# finger_circuit.net
KiCad netlist of a schematic drawn in EAGLE
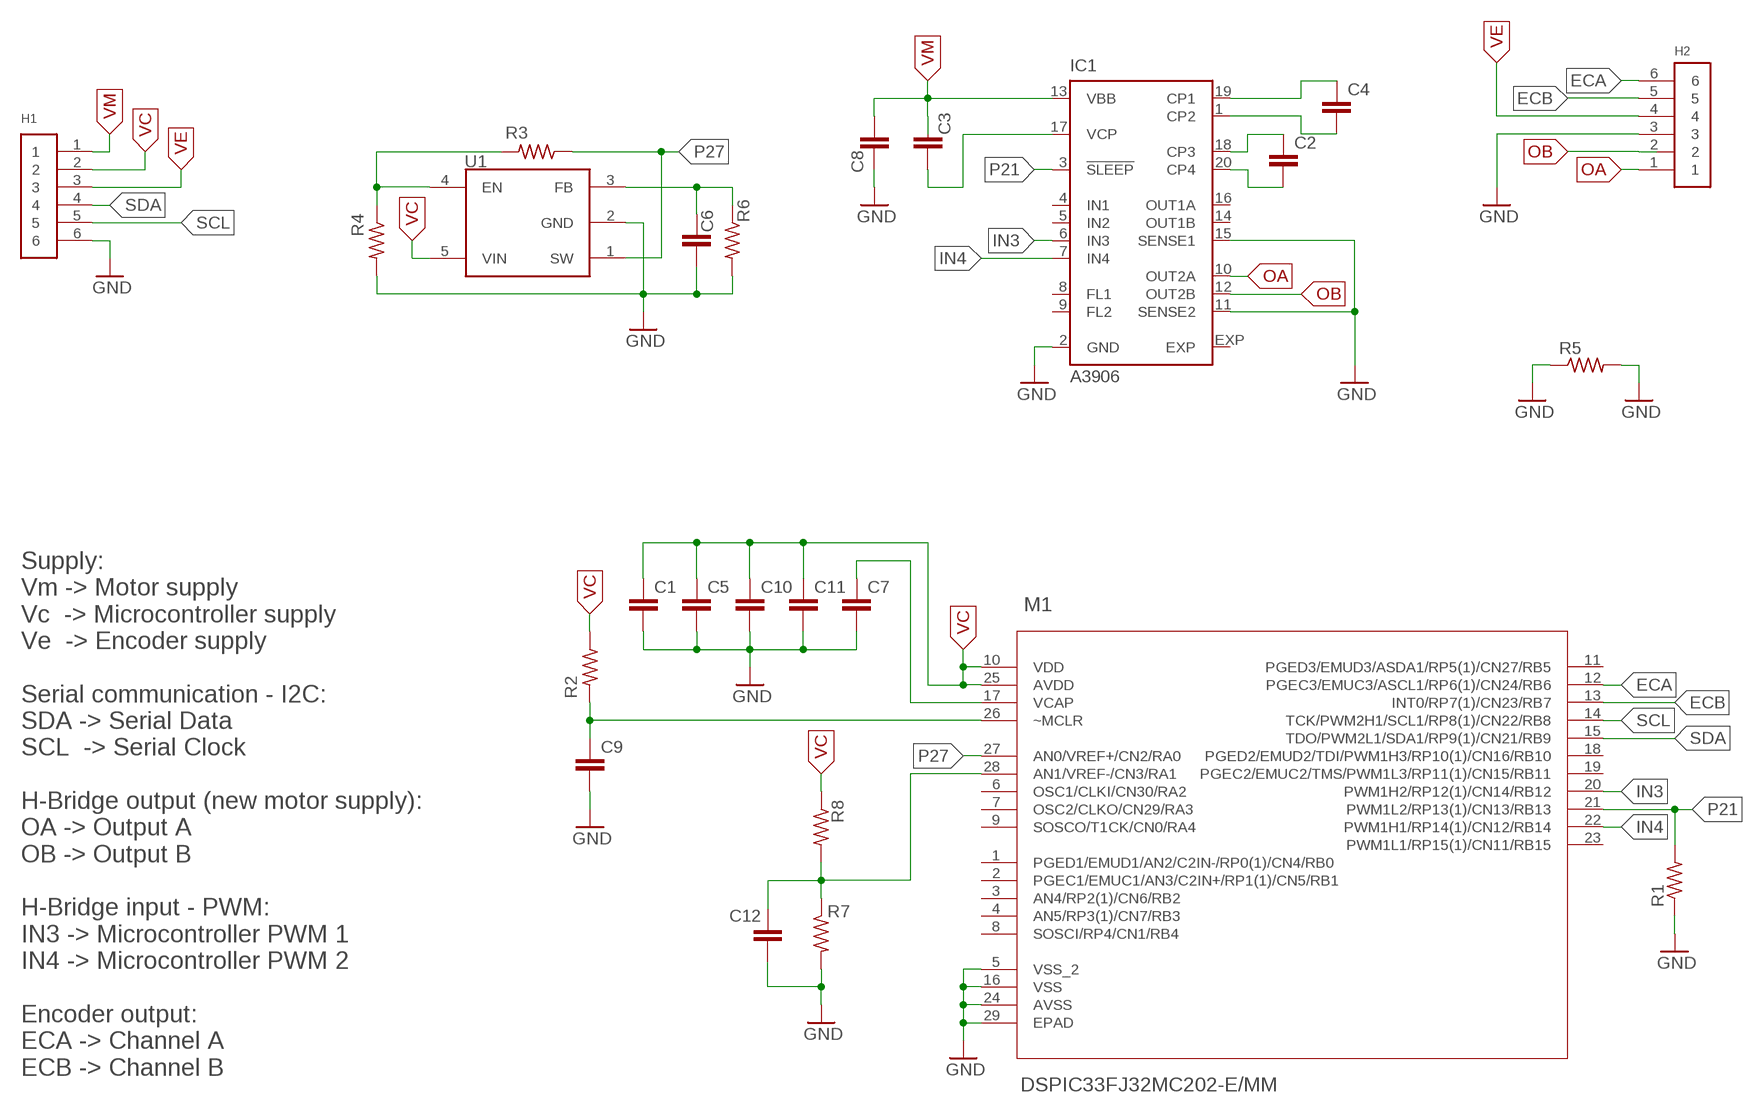
[diagram p0: schematic, sheet 1]

(export (version "E")
  (design (tool "Eeschema 10.0.6"))
  (components
    (comp (ref "C1")
      (value "CAPACITOR_0805_M")
      (footprint "eagle-import:RESC0805_M")
      (libsource (lib "eagle-import") (part "CAPACITOR_0805_M"))
    )
    (comp (ref "C2")
      (value "CAPACITOR_0805_M")
      (footprint "eagle-import:RESC0805_M")
      (libsource (lib "eagle-import") (part "CAPACITOR_0805_M"))
    )
    (comp (ref "C3")
      (value "CAPACITOR_0805_M")
      (footprint "eagle-import:RESC0805_M")
      (libsource (lib "eagle-import") (part "CAPACITOR_0805_M"))
    )
    (comp (ref "C4")
      (value "CAPACITOR_0805_M")
      (footprint "eagle-import:RESC0805_M")
      (libsource (lib "eagle-import") (part "CAPACITOR_0805_M"))
    )
    (comp (ref "C5")
      (value "CAPACITOR_0805_M")
      (footprint "eagle-import:RESC0805_M")
      (libsource (lib "eagle-import") (part "CAPACITOR_0805_M"))
    )
    (comp (ref "C6")
      (value "CAPACITOR_0805_M")
      (footprint "eagle-import:RESC0805_M")
      (libsource (lib "eagle-import") (part "CAPACITOR_0805_M"))
    )
    (comp (ref "C7")
      (value "CAPACITOR_0805_M")
      (footprint "eagle-import:RESC0805_M")
      (libsource (lib "eagle-import") (part "CAPACITOR_0805_M"))
    )
    (comp (ref "C8")
      (value "CAPACITOR_0805_M")
      (footprint "eagle-import:RESC0805_M")
      (libsource (lib "eagle-import") (part "CAPACITOR_0805_M"))
    )
    (comp (ref "C9")
      (value "CAPACITOR_0805_M")
      (footprint "eagle-import:RESC0805_M")
      (libsource (lib "eagle-import") (part "CAPACITOR_0805_M"))
    )
    (comp (ref "C10")
      (value "CAPACITOR_0805_M")
      (footprint "eagle-import:RESC0805_M")
      (libsource (lib "eagle-import") (part "CAPACITOR_0805_M"))
    )
    (comp (ref "C11")
      (value "CAPACITOR_0805_M")
      (footprint "eagle-import:RESC0805_M")
      (libsource (lib "eagle-import") (part "CAPACITOR_0805_M"))
    )
    (comp (ref "C12")
      (value "CAPACITOR_0805_M")
      (footprint "eagle-import:RESC0805_M")
      (libsource (lib "eagle-import") (part "CAPACITOR_0805_M"))
    )
    (comp (ref "H1")
      (value "61300611121")
      (footprint "eagle-import:61300611121")
      (fields
        (field (name "DIGI_KEY_PART_NUMBER") "732-5319-ND")
        (field (name "MANUFACTURER") "Wurth Electronics Inc.")
        (field (name "CREATED_BY") "PCBLayout.com")
      )
      (libsource (lib "eagle-import") (part "61300611121"))
    )
    (comp (ref "H2")
      (value "61300611121")
      (footprint "eagle-import:61300611121")
      (fields
        (field (name "DIGI_KEY_PART_NUMBER") "732-5319-ND")
        (field (name "MANUFACTURER") "Wurth Electronics Inc.")
        (field (name "CREATED_BY") "PCBLayout.com")
      )
      (libsource (lib "eagle-import") (part "61300611121"))
    )
    (comp (ref "IC1")
      (value "A3906")
      (footprint "eagle-import:QFN20")
      (libsource (lib "eagle-import") (part "A3906"))
    )
    (comp (ref "M1")
      (value "DSPIC33FJ32MC202-E/MM")
      (footprint "eagle-import:QFN65P600X600X100-29N")
      (fields
        (field (name "DIGI-KEY_PART_NUMBER") "DSPIC33FJ32MC202-E/MM-ND")
        (field (name "MF") "Microchip")
      )
      (libsource (lib "eagle-import") (part "DSPIC33FJ32MC202-E/MM"))
    )
    (comp (ref "R1")
      (value "R-US_R0805")
      (footprint "eagle-import:R0805")
      (libsource (lib "eagle-import") (part "R-US_R0805"))
    )
    (comp (ref "R2")
      (value "R-US_R0805")
      (footprint "eagle-import:R0805")
      (libsource (lib "eagle-import") (part "R-US_R0805"))
    )
    (comp (ref "R3")
      (value "R-US_R0805")
      (footprint "eagle-import:R0805")
      (libsource (lib "eagle-import") (part "R-US_R0805"))
    )
    (comp (ref "R4")
      (value "R-US_R0805")
      (footprint "eagle-import:R0805")
      (libsource (lib "eagle-import") (part "R-US_R0805"))
    )
    (comp (ref "R5")
      (value "R-US_R0805")
      (footprint "eagle-import:R0805")
      (libsource (lib "eagle-import") (part "R-US_R0805"))
    )
    (comp (ref "R6")
      (value "R-US_R0805")
      (footprint "eagle-import:R0805")
      (libsource (lib "eagle-import") (part "R-US_R0805"))
    )
    (comp (ref "R7")
      (value "R-US_R0805")
      (footprint "eagle-import:R0805")
      (libsource (lib "eagle-import") (part "R-US_R0805"))
    )
    (comp (ref "R8")
      (value "R-US_R0805")
      (footprint "eagle-import:R0805")
      (libsource (lib "eagle-import") (part "R-US_R0805"))
    )
    (comp (ref "U1")
      (value "LMR10510")
      (footprint "eagle-import:SOT-23-5")
      (fields
        (field (name "DIGIKEY_PART_NUMBER") "LMR10510YMFE/NOPBTR-ND")
        (field (name "MANUFACTURER") "Texas Instruments")
        (field (name "MPN") "LMR10510YMFE/NOPB")
        (field (name "CREATED_BY") "PCBLayout.com")
      )
      (libsource (lib "eagle-import") (part "LMR10510YMFE/NOPB"))
    )
  )
  (nets
    (net (code "1") (name "ECA") (class "Default")
      (node (ref "H2") (pin "6") (pinfunction "6_6") (pintype "passive"))
      (node (ref "M1") (pin "12") (pinfunction "PGEC3/EMUC3/ASCL1/RP6(1)/CN24/RB6_12") (pintype "bidirectional"))
    )
    (net (code "2") (name "ECB") (class "Default")
      (node (ref "H2") (pin "5") (pinfunction "5_5") (pintype "passive"))
      (node (ref "M1") (pin "13") (pinfunction "INT0/RP7(1)/CN23/RB7_13") (pintype "bidirectional"))
    )
    (net (code "3") (name "GND") (class "Default")
      (node (ref "C1") (pin "2") (pinfunction "2_2") (pintype "passive"))
      (node (ref "C10") (pin "2") (pinfunction "2_2") (pintype "passive"))
      (node (ref "C11") (pin "2") (pinfunction "2_2") (pintype "passive"))
      (node (ref "C12") (pin "2") (pinfunction "2_2") (pintype "passive"))
      (node (ref "C5") (pin "2") (pinfunction "2_2") (pintype "passive"))
      (node (ref "C6") (pin "2") (pinfunction "2_2") (pintype "passive"))
      (node (ref "C7") (pin "2") (pinfunction "2_2") (pintype "passive"))
      (node (ref "C8") (pin "1") (pinfunction "1_1") (pintype "passive"))
      (node (ref "C9") (pin "2") (pinfunction "2_2") (pintype "passive"))
      (node (ref "H1") (pin "6") (pinfunction "6_6") (pintype "passive"))
      (node (ref "H2") (pin "3") (pinfunction "3_3") (pintype "passive"))
      (node (ref "IC1") (pin "11") (pinfunction "SENSE2_11") (pintype "input"))
      (node (ref "IC1") (pin "15") (pinfunction "SENSE1_15") (pintype "input"))
      (node (ref "IC1") (pin "2") (pinfunction "GND_2") (pintype "power_in"))
      (node (ref "M1") (pin "16") (pinfunction "VSS_16") (pintype "power_in"))
      (node (ref "M1") (pin "24") (pinfunction "AVSS_24") (pintype "power_in"))
      (node (ref "M1") (pin "29") (pinfunction "EPAD_29") (pintype "passive"))
      (node (ref "M1") (pin "5") (pinfunction "VSS_2_5") (pintype "power_in"))
      (node (ref "R1") (pin "1") (pinfunction "1_1") (pintype "passive"))
      (node (ref "R4") (pin "2") (pinfunction "2_2") (pintype "passive"))
      (node (ref "R5") (pin "1") (pinfunction "1_1") (pintype "passive"))
      (node (ref "R5") (pin "2") (pinfunction "2_2") (pintype "passive"))
      (node (ref "R6") (pin "2") (pinfunction "2_2") (pintype "passive"))
      (node (ref "R7") (pin "2") (pinfunction "2_2") (pintype "passive"))
      (node (ref "U1") (pin "2") (pinfunction "GND_2") (pintype "power_in"))
    )
    (net (code "4") (name "IN3") (class "Default")
      (node (ref "IC1") (pin "6") (pinfunction "IN3_6") (pintype "input"))
      (node (ref "M1") (pin "20") (pinfunction "PWM1H2/RP12(1)/CN14/RB12_20") (pintype "bidirectional"))
    )
    (net (code "5") (name "IN4") (class "Default")
      (node (ref "IC1") (pin "7") (pinfunction "IN4_7") (pintype "input"))
      (node (ref "M1") (pin "22") (pinfunction "PWM1H1/RP14(1)/CN12/RB14_22") (pintype "bidirectional"))
    )
    (net (code "6") (name "Net-(IC1-CP1)") (class "Default")
      (node (ref "C4") (pin "1") (pinfunction "1_1") (pintype "passive"))
      (node (ref "IC1") (pin "19") (pinfunction "CP1_19") (pintype "passive"))
    )
    (net (code "7") (name "Net-(IC1-CP2)") (class "Default")
      (node (ref "C4") (pin "2") (pinfunction "2_2") (pintype "passive"))
      (node (ref "IC1") (pin "1") (pinfunction "CP2_1") (pintype "passive"))
    )
    (net (code "8") (name "Net-(IC1-CP3)") (class "Default")
      (node (ref "C2") (pin "1") (pinfunction "1_1") (pintype "passive"))
      (node (ref "IC1") (pin "18") (pinfunction "CP3_18") (pintype "passive"))
    )
    (net (code "9") (name "Net-(IC1-CP4)") (class "Default")
      (node (ref "C2") (pin "2") (pinfunction "2_2") (pintype "passive"))
      (node (ref "IC1") (pin "20") (pinfunction "CP4_20") (pintype "passive"))
    )
    (net (code "10") (name "Net-(IC1-VCP)") (class "Default")
      (node (ref "C3") (pin "2") (pinfunction "2_2") (pintype "passive"))
      (node (ref "IC1") (pin "17") (pinfunction "VCP_17") (pintype "passive"))
    )
    (net (code "11") (name "Net-(M1-AN1{slash}VREF-{slash}CN3{slash}RA1)") (class "Default")
      (node (ref "C12") (pin "1") (pinfunction "1_1") (pintype "passive"))
      (node (ref "M1") (pin "28") (pinfunction "AN1/VREF-/CN3/RA1_28") (pintype "bidirectional"))
      (node (ref "R7") (pin "1") (pinfunction "1_1") (pintype "passive"))
      (node (ref "R8") (pin "2") (pinfunction "2_2") (pintype "passive"))
    )
    (net (code "12") (name "Net-(M1-VCAP)") (class "Default")
      (node (ref "C7") (pin "1") (pinfunction "1_1") (pintype "passive"))
      (node (ref "M1") (pin "17") (pinfunction "VCAP_17") (pintype "power_in"))
    )
    (net (code "13") (name "Net-(M1-~{MCLR})") (class "Default")
      (node (ref "C9") (pin "1") (pinfunction "1_1") (pintype "passive"))
      (node (ref "M1") (pin "26") (pinfunction "~{MCLR}_26") (pintype "input"))
      (node (ref "R2") (pin "2") (pinfunction "2_2") (pintype "passive"))
    )
    (net (code "14") (name "Net-(U1-EN)") (class "Default")
      (node (ref "R3") (pin "2") (pinfunction "2_2") (pintype "passive"))
      (node (ref "R4") (pin "1") (pinfunction "1_1") (pintype "passive"))
      (node (ref "U1") (pin "4") (pinfunction "EN_4") (pintype "input"))
    )
    (net (code "15") (name "Net-(U1-FB)") (class "Default")
      (node (ref "C6") (pin "1") (pinfunction "1_1") (pintype "passive"))
      (node (ref "R6") (pin "1") (pinfunction "1_1") (pintype "passive"))
      (node (ref "U1") (pin "3") (pinfunction "FB_3") (pintype "output"))
    )
    (net (code "16") (name "OA") (class "Default")
      (node (ref "H2") (pin "1") (pinfunction "1_1") (pintype "passive"))
      (node (ref "IC1") (pin "10") (pinfunction "OUT2A_10") (pintype "output"))
    )
    (net (code "17") (name "OB") (class "Default")
      (node (ref "H2") (pin "2") (pinfunction "2_2") (pintype "passive"))
      (node (ref "IC1") (pin "12") (pinfunction "OUT2B_12") (pintype "output"))
    )
    (net (code "18") (name "P21") (class "Default")
      (node (ref "IC1") (pin "3") (pinfunction "~{SLEEP}_3") (pintype "input"))
      (node (ref "M1") (pin "21") (pinfunction "PWM1L2/RP13(1)/CN13/RB13_21") (pintype "bidirectional"))
      (node (ref "R1") (pin "2") (pinfunction "2_2") (pintype "passive"))
    )
    (net (code "19") (name "P27") (class "Default")
      (node (ref "M1") (pin "27") (pinfunction "AN0/VREF+/CN2/RA0_27") (pintype "bidirectional"))
      (node (ref "R3") (pin "1") (pinfunction "1_1") (pintype "passive"))
      (node (ref "U1") (pin "1") (pinfunction "SW_1") (pintype "bidirectional"))
    )
    (net (code "20") (name "SCL") (class "Default")
      (node (ref "H1") (pin "5") (pinfunction "5_5") (pintype "passive"))
      (node (ref "M1") (pin "14") (pinfunction "TCK/PWM2H1/SCL1/RP8(1)/CN22/RB8_14") (pintype "bidirectional"))
    )
    (net (code "21") (name "SDA") (class "Default")
      (node (ref "H1") (pin "4") (pinfunction "4_4") (pintype "passive"))
      (node (ref "M1") (pin "15") (pinfunction "TDO/PWM2L1/SDA1/RP9(1)/CN21/RB9_15") (pintype "bidirectional"))
    )
    (net (code "22") (name "VC") (class "Default")
      (node (ref "C1") (pin "1") (pinfunction "1_1") (pintype "passive"))
      (node (ref "C10") (pin "1") (pinfunction "1_1") (pintype "passive"))
      (node (ref "C11") (pin "1") (pinfunction "1_1") (pintype "passive"))
      (node (ref "C5") (pin "1") (pinfunction "1_1") (pintype "passive"))
      (node (ref "H1") (pin "2") (pinfunction "2_2") (pintype "passive"))
      (node (ref "M1") (pin "10") (pinfunction "VDD_10") (pintype "power_in"))
      (node (ref "M1") (pin "25") (pinfunction "AVDD_25") (pintype "power_in"))
      (node (ref "R2") (pin "1") (pinfunction "1_1") (pintype "passive"))
      (node (ref "R8") (pin "1") (pinfunction "1_1") (pintype "passive"))
      (node (ref "U1") (pin "5") (pinfunction "VIN_5") (pintype "power_in"))
    )
    (net (code "23") (name "VE") (class "Default")
      (node (ref "H1") (pin "3") (pinfunction "3_3") (pintype "passive"))
      (node (ref "H2") (pin "4") (pinfunction "4_4") (pintype "passive"))
    )
    (net (code "24") (name "VM") (class "Default")
      (node (ref "C3") (pin "1") (pinfunction "1_1") (pintype "passive"))
      (node (ref "C8") (pin "2") (pinfunction "2_2") (pintype "passive"))
      (node (ref "H1") (pin "1") (pinfunction "1_1") (pintype "passive"))
      (node (ref "IC1") (pin "13") (pinfunction "VBB_13") (pintype "power_in"))
    )
    (net (code "25") (name "unconnected-(IC1-FL1-Pad8)") (class "Default")
      (node (ref "IC1") (pin "8") (pinfunction "FL1_8") (pintype "input"))
    )
    (net (code "26") (name "unconnected-(IC1-FL2-Pad9)") (class "Default")
      (node (ref "IC1") (pin "9") (pinfunction "FL2_9") (pintype "input"))
    )
    (net (code "27") (name "unconnected-(IC1-IN1-Pad4)") (class "Default")
      (node (ref "IC1") (pin "4") (pinfunction "IN1_4") (pintype "input"))
    )
    (net (code "28") (name "unconnected-(IC1-IN2-Pad5)") (class "Default")
      (node (ref "IC1") (pin "5") (pinfunction "IN2_5") (pintype "input"))
    )
    (net (code "29") (name "unconnected-(IC1-OUT1A-Pad16)") (class "Default")
      (node (ref "IC1") (pin "16") (pinfunction "OUT1A_16") (pintype "output"))
    )
    (net (code "30") (name "unconnected-(IC1-OUT1B-Pad14)") (class "Default")
      (node (ref "IC1") (pin "14") (pinfunction "OUT1B_14") (pintype "output"))
    )
    (net (code "31") (name "unconnected-(IC1-PadEXP)") (class "Default")
      (node (ref "IC1") (pin "EXP") (pinfunction "EXP_EXP") (pintype "passive"))
    )
    (net (code "32") (name "unconnected-(M1-AN4{slash}RP2(1){slash}CN6{slash}RB2-Pad3)") (class "Default")
      (node (ref "M1") (pin "3") (pinfunction "AN4/RP2(1)/CN6/RB2_3") (pintype "bidirectional"))
    )
    (net (code "33") (name "unconnected-(M1-AN5{slash}RP3(1){slash}CN7{slash}RB3-Pad4)") (class "Default")
      (node (ref "M1") (pin "4") (pinfunction "AN5/RP3(1)/CN7/RB3_4") (pintype "bidirectional"))
    )
    (net (code "34") (name "unconnected-(M1-OSC1{slash}CLKI{slash}CN30{slash}RA2-Pad6)") (class "Default")
      (node (ref "M1") (pin "6") (pinfunction "OSC1/CLKI/CN30/RA2_6") (pintype "bidirectional"))
    )
    (net (code "35") (name "unconnected-(M1-OSC2{slash}CLKO{slash}CN29{slash}RA3-Pad7)") (class "Default")
      (node (ref "M1") (pin "7") (pinfunction "OSC2/CLKO/CN29/RA3_7") (pintype "bidirectional"))
    )
    (net (code "36") (name "unconnected-(M1-PGEC1{slash}EMUC1{slash}AN3{slash}C2IN+{slash}RP1(1){slash}CN5{slash}RB1-Pad2)") (class "Default")
      (node (ref "M1") (pin "2") (pinfunction "PGEC1/EMUC1/AN3/C2IN+/RP1(1)/CN5/RB1_2") (pintype "bidirectional"))
    )
    (net (code "37") (name "unconnected-(M1-PGEC2{slash}EMUC2{slash}TMS{slash}PWM1L3{slash}RP11(1){slash}CN15{slash}RB11-Pad19)") (class "Default")
      (node (ref "M1") (pin "19") (pinfunction "PGEC2/EMUC2/TMS/PWM1L3/RP11(1)/CN15/RB11_19") (pintype "bidirectional"))
    )
    (net (code "38") (name "unconnected-(M1-PGED1{slash}EMUD1{slash}AN2{slash}C2IN-{slash}RP0(1){slash}CN4{slash}RB0-Pad1)") (class "Default")
      (node (ref "M1") (pin "1") (pinfunction "PGED1/EMUD1/AN2/C2IN-/RP0(1)/CN4/RB0_1") (pintype "bidirectional"))
    )
    (net (code "39") (name "unconnected-(M1-PGED2{slash}EMUD2{slash}TDI{slash}PWM1H3{slash}RP10(1){slash}CN16{slash}RB10-Pad18)") (class "Default")
      (node (ref "M1") (pin "18") (pinfunction "PGED2/EMUD2/TDI/PWM1H3/RP10(1)/CN16/RB10_18") (pintype "bidirectional"))
    )
    (net (code "40") (name "unconnected-(M1-PGED3{slash}EMUD3{slash}ASDA1{slash}RP5(1){slash}CN27{slash}RB5-Pad11)") (class "Default")
      (node (ref "M1") (pin "11") (pinfunction "PGED3/EMUD3/ASDA1/RP5(1)/CN27/RB5_11") (pintype "bidirectional"))
    )
    (net (code "41") (name "unconnected-(M1-PWM1L1{slash}RP15(1){slash}CN11{slash}RB15-Pad23)") (class "Default")
      (node (ref "M1") (pin "23") (pinfunction "PWM1L1/RP15(1)/CN11/RB15_23") (pintype "bidirectional"))
    )
    (net (code "42") (name "unconnected-(M1-SOSCI{slash}RP4{slash}CN1{slash}RB4-Pad8)") (class "Default")
      (node (ref "M1") (pin "8") (pinfunction "SOSCI/RP4/CN1/RB4_8") (pintype "bidirectional"))
    )
    (net (code "43") (name "unconnected-(M1-SOSCO{slash}T1CK{slash}CN0{slash}RA4-Pad9)") (class "Default")
      (node (ref "M1") (pin "9") (pinfunction "SOSCO/T1CK/CN0/RA4_9") (pintype "bidirectional"))
    )
  )
)
